# SparkFun_MMA8452Q-Breakout.net
KiCad netlist of a schematic drawn in EAGLE
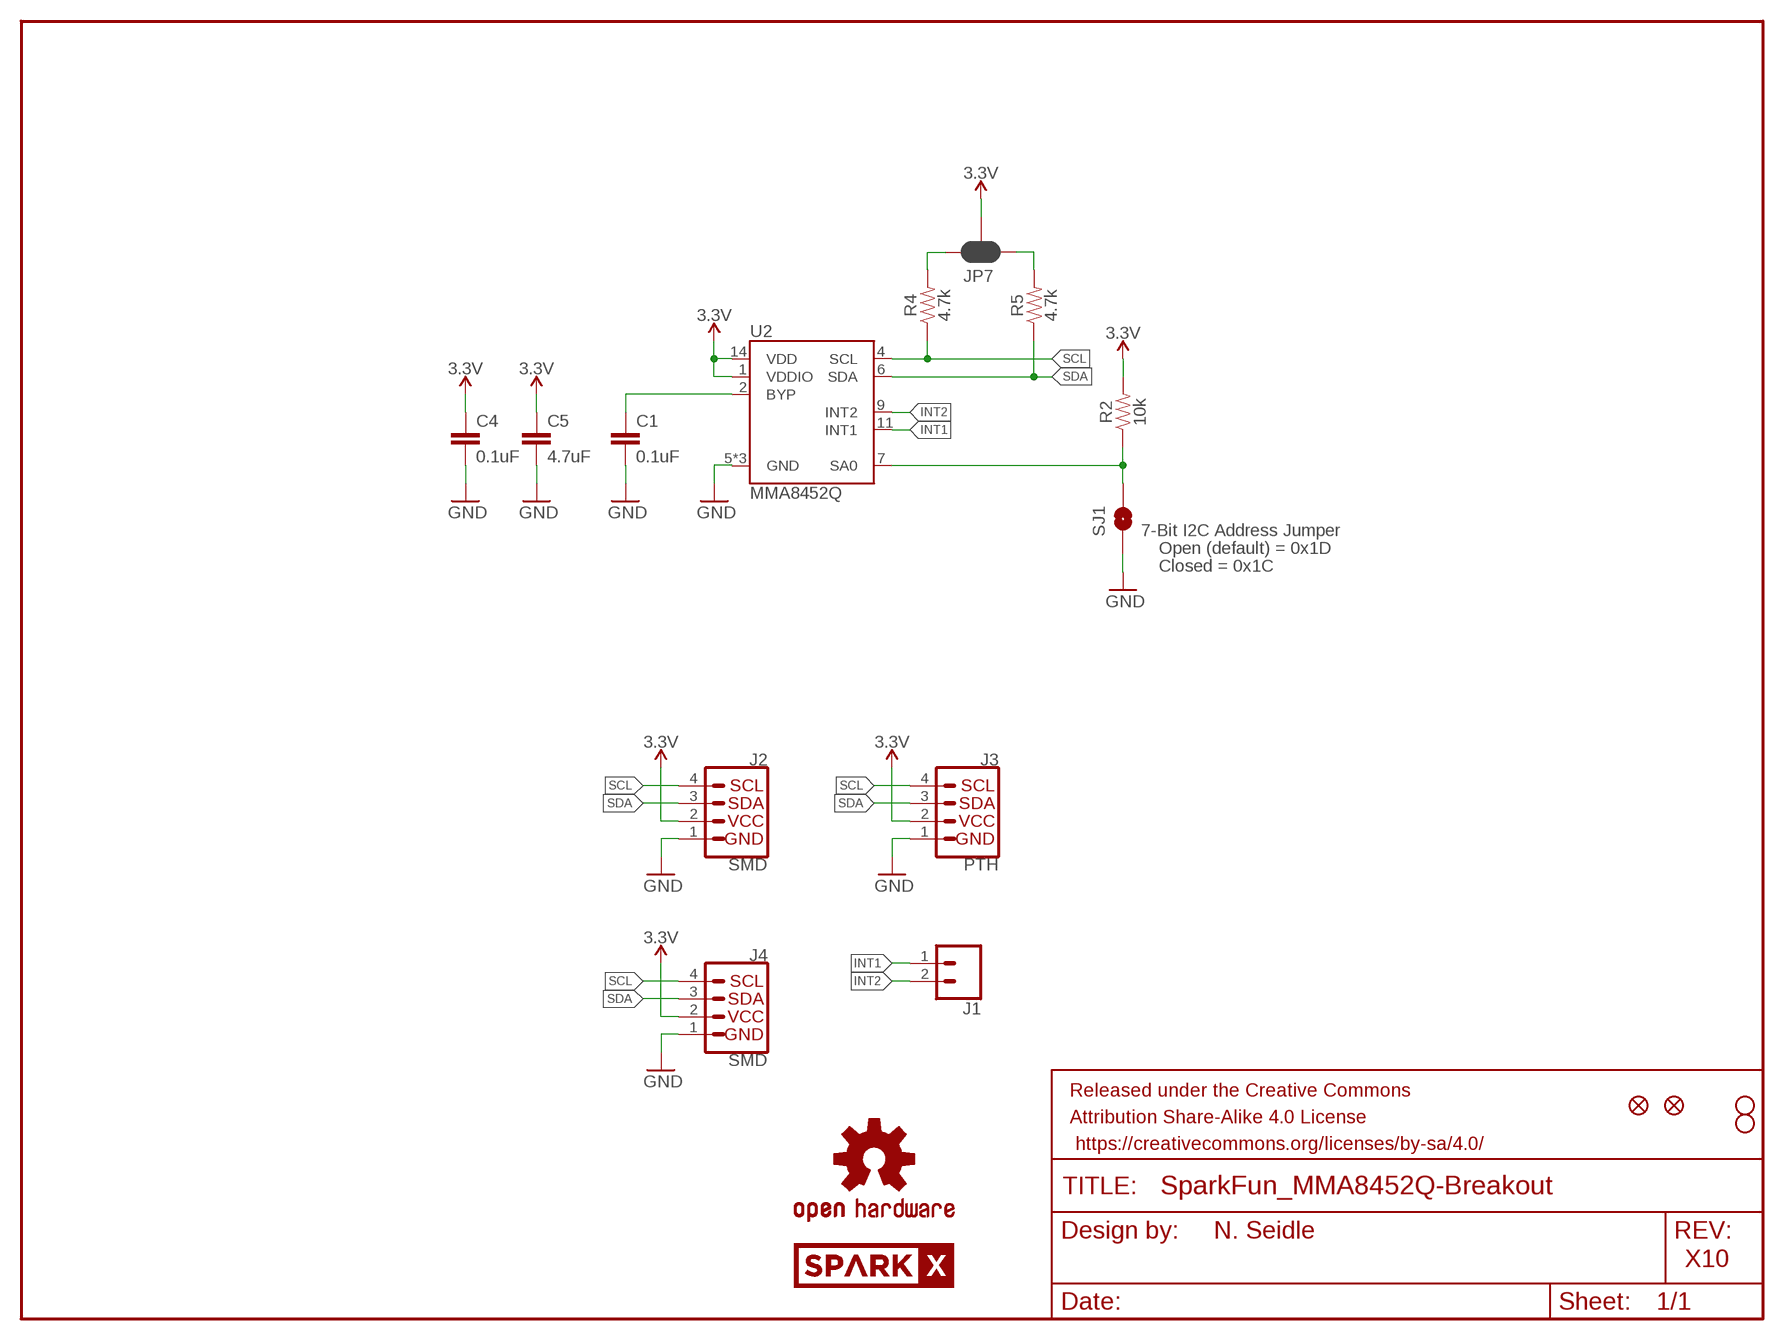
[diagram p0: schematic, sheet 1]

(export (version "E")
  (design (tool "Eeschema 10.0.6"))
  (components
    (comp (ref "C1")
      (value "0.1uF")
      (footprint "eagle-import:0603")
      (libsource (lib "eagle-import") (part "0.1UF-0603-25V-(+80/-20%)"))
    )
    (comp (ref "C4")
      (value "0.1uF")
      (footprint "eagle-import:0603")
      (libsource (lib "eagle-import") (part "0.1UF-0603-25V-(+80/-20%)"))
    )
    (comp (ref "C5")
      (value "4.7uF")
      (footprint "eagle-import:0603")
      (libsource (lib "eagle-import") (part "4.7UF0603"))
    )
    (comp (ref "FRAME1")
      (value "FRAME-LETTER")
      (footprint "eagle-import:CREATIVE_COMMONS")
      (libsource (lib "eagle-import") (part "FRAME-LETTER"))
    )
    (comp (ref "J1")
      (value "CONN_021X02_NO_SILK")
      (footprint "eagle-import:1X02_NO_SILK")
      (libsource (lib "eagle-import") (part "CONN_021X02_NO_SILK"))
    )
    (comp (ref "J2")
      (value "SMD")
      (footprint "eagle-import:1X04_1MM_RA")
      (libsource (lib "eagle-import") (part "I2C_STANDARDJS-1MM"))
    )
    (comp (ref "J3")
      (value "PTH")
      (footprint "eagle-import:1X04_NO_SILK")
      (libsource (lib "eagle-import") (part "I2C_STANDARD_NO_SILK"))
    )
    (comp (ref "J4")
      (value "SMD")
      (footprint "eagle-import:1X04_1MM_RA")
      (libsource (lib "eagle-import") (part "I2C_STANDARDJS-1MM"))
    )
    (comp (ref "JP2")
      (value "FIDUCIALUFIDUCIAL")
      (footprint "eagle-import:MICRO-FIDUCIAL")
      (libsource (lib "eagle-import") (part "FIDUCIALUFIDUCIAL"))
    )
    (comp (ref "JP3")
      (value "STAND-OFF")
      (footprint "eagle-import:STAND-OFF")
      (libsource (lib "eagle-import") (part "STAND-OFF"))
    )
    (comp (ref "JP4")
      (value "STAND-OFF")
      (footprint "eagle-import:STAND-OFF")
      (libsource (lib "eagle-import") (part "STAND-OFF"))
    )
    (comp (ref "JP6")
      (value "FIDUCIALUFIDUCIAL")
      (footprint "eagle-import:MICRO-FIDUCIAL")
      (libsource (lib "eagle-import") (part "FIDUCIALUFIDUCIAL"))
    )
    (comp (ref "JP7")
      (value "JUMPER-SMT_3_2-NC_PASTE_SILK")
      (footprint "eagle-import:SMT-JUMPER_3_2-NC_PASTE_SILK")
      (libsource (lib "eagle-import") (part "JUMPER-SMT_3_2-NC_PASTE_SILK"))
    )
    (comp (ref "LOGO1")
      (value "OSHW-LOGOMINI")
      (footprint "eagle-import:OSHW-LOGO-MINI")
      (libsource (lib "eagle-import") (part "OSHW-LOGOMINI"))
    )
    (comp (ref "R2")
      (value "10k")
      (footprint "eagle-import:0603")
      (libsource (lib "eagle-import") (part "10KOHM-0603-1/10W-1%"))
    )
    (comp (ref "R4")
      (value "4.7k")
      (footprint "eagle-import:0603")
      (libsource (lib "eagle-import") (part "4.7KOHM-0603-1/10W-1%"))
    )
    (comp (ref "R5")
      (value "4.7k")
      (footprint "eagle-import:0603")
      (libsource (lib "eagle-import") (part "4.7KOHM-0603-1/10W-1%"))
    )
    (comp (ref "SJ1")
      (value "SOLDERJUMPERNO")
      (footprint "eagle-import:SJ_2S-NO")
      (libsource (lib "eagle-import") (part "SOLDERJUMPERNO"))
    )
    (comp (ref "U$1")
      (value "SPARKX-LOGO4")
      (footprint "eagle-import:SPARKX-MEDIUM")
      (libsource (lib "eagle-import") (part "SPARKX-LOGO4"))
    )
    (comp (ref "U$2")
      (value "SPARKX-LOGO4")
      (footprint "eagle-import:SPARKX-MEDIUM")
      (libsource (lib "eagle-import") (part "SPARKX-LOGO4"))
    )
    (comp (ref "U2")
      (value "MMA8452Q")
      (footprint "eagle-import:QFN-16_0.5MM")
      (libsource (lib "eagle-import") (part "MMA8452Q"))
    )
  )
  (nets
    (net (code "1") (name "3.3V") (class "Default")
      (node (ref "C4") (pin "1") (pinfunction "1_1") (pintype "passive"))
      (node (ref "C5") (pin "1") (pinfunction "1_1") (pintype "passive"))
      (node (ref "J2") (pin "2") (pinfunction "VCC_2") (pintype "power_in"))
      (node (ref "J3") (pin "2") (pinfunction "VCC_2") (pintype "power_in"))
      (node (ref "J4") (pin "2") (pinfunction "VCC_2") (pintype "power_in"))
      (node (ref "JP7") (pin "2") (pinfunction "2_2") (pintype "passive"))
      (node (ref "R2") (pin "2") (pinfunction "2_2") (pintype "passive"))
      (node (ref "U2") (pin "1") (pinfunction "VDDIO_1") (pintype "bidirectional"))
      (node (ref "U2") (pin "14") (pinfunction "VDD_14") (pintype "bidirectional"))
    )
    (net (code "2") (name "GND") (class "Default")
      (node (ref "C1") (pin "2") (pinfunction "2_2") (pintype "passive"))
      (node (ref "C4") (pin "2") (pinfunction "2_2") (pintype "passive"))
      (node (ref "C5") (pin "2") (pinfunction "2_2") (pintype "passive"))
      (node (ref "J2") (pin "1") (pinfunction "GND_1") (pintype "power_in"))
      (node (ref "J3") (pin "1") (pinfunction "GND_1") (pintype "power_in"))
      (node (ref "J4") (pin "1") (pinfunction "GND_1") (pintype "power_in"))
      (node (ref "SJ1") (pin "1") (pinfunction "1_1") (pintype "passive"))
      (node (ref "U2") (pin "10") (pinfunction "GND_10") (pintype "bidirectional"))
      (node (ref "U2") (pin "12") (pinfunction "GND_12") (pintype "bidirectional"))
      (node (ref "U2") (pin "5") (pinfunction "GND_5") (pintype "bidirectional"))
    )
    (net (code "3") (name "INT1") (class "Default")
      (node (ref "J1") (pin "1") (pinfunction "1_1") (pintype "passive"))
      (node (ref "U2") (pin "11") (pinfunction "INT1_11") (pintype "bidirectional"))
    )
    (net (code "4") (name "INT2") (class "Default")
      (node (ref "J1") (pin "2") (pinfunction "2_2") (pintype "passive"))
      (node (ref "U2") (pin "9") (pinfunction "INT2_9") (pintype "bidirectional"))
    )
    (net (code "5") (name "Net-(JP7-Pad1)") (class "Default")
      (node (ref "JP7") (pin "1") (pinfunction "1_1") (pintype "passive"))
      (node (ref "R5") (pin "2") (pinfunction "2_2") (pintype "passive"))
    )
    (net (code "6") (name "Net-(JP7-Pad3)") (class "Default")
      (node (ref "JP7") (pin "3") (pinfunction "3_3") (pintype "passive"))
      (node (ref "R4") (pin "2") (pinfunction "2_2") (pintype "passive"))
    )
    (net (code "7") (name "Net-(U2-BYP)") (class "Default")
      (node (ref "C1") (pin "1") (pinfunction "1_1") (pintype "passive"))
      (node (ref "U2") (pin "2") (pinfunction "BYP_2") (pintype "bidirectional"))
    )
    (net (code "8") (name "Net-(U2-SA0)") (class "Default")
      (node (ref "R2") (pin "1") (pinfunction "1_1") (pintype "passive"))
      (node (ref "SJ1") (pin "2") (pinfunction "2_2") (pintype "passive"))
      (node (ref "U2") (pin "7") (pinfunction "SA0_7") (pintype "bidirectional"))
    )
    (net (code "9") (name "SCL") (class "Default")
      (node (ref "J2") (pin "4") (pinfunction "SCL_4") (pintype "passive"))
      (node (ref "J3") (pin "4") (pinfunction "SCL_4") (pintype "passive"))
      (node (ref "J4") (pin "4") (pinfunction "SCL_4") (pintype "passive"))
      (node (ref "R4") (pin "1") (pinfunction "1_1") (pintype "passive"))
      (node (ref "U2") (pin "4") (pinfunction "SCL_4") (pintype "bidirectional"))
    )
    (net (code "10") (name "SDA") (class "Default")
      (node (ref "J2") (pin "3") (pinfunction "SDA_3") (pintype "passive"))
      (node (ref "J3") (pin "3") (pinfunction "SDA_3") (pintype "passive"))
      (node (ref "J4") (pin "3") (pinfunction "SDA_3") (pintype "passive"))
      (node (ref "R5") (pin "1") (pinfunction "1_1") (pintype "passive"))
      (node (ref "U2") (pin "6") (pinfunction "SDA_6") (pintype "bidirectional"))
    )
  )
)
